# Root_v1_01.net
KiCad netlist of a schematic drawn in EAGLE
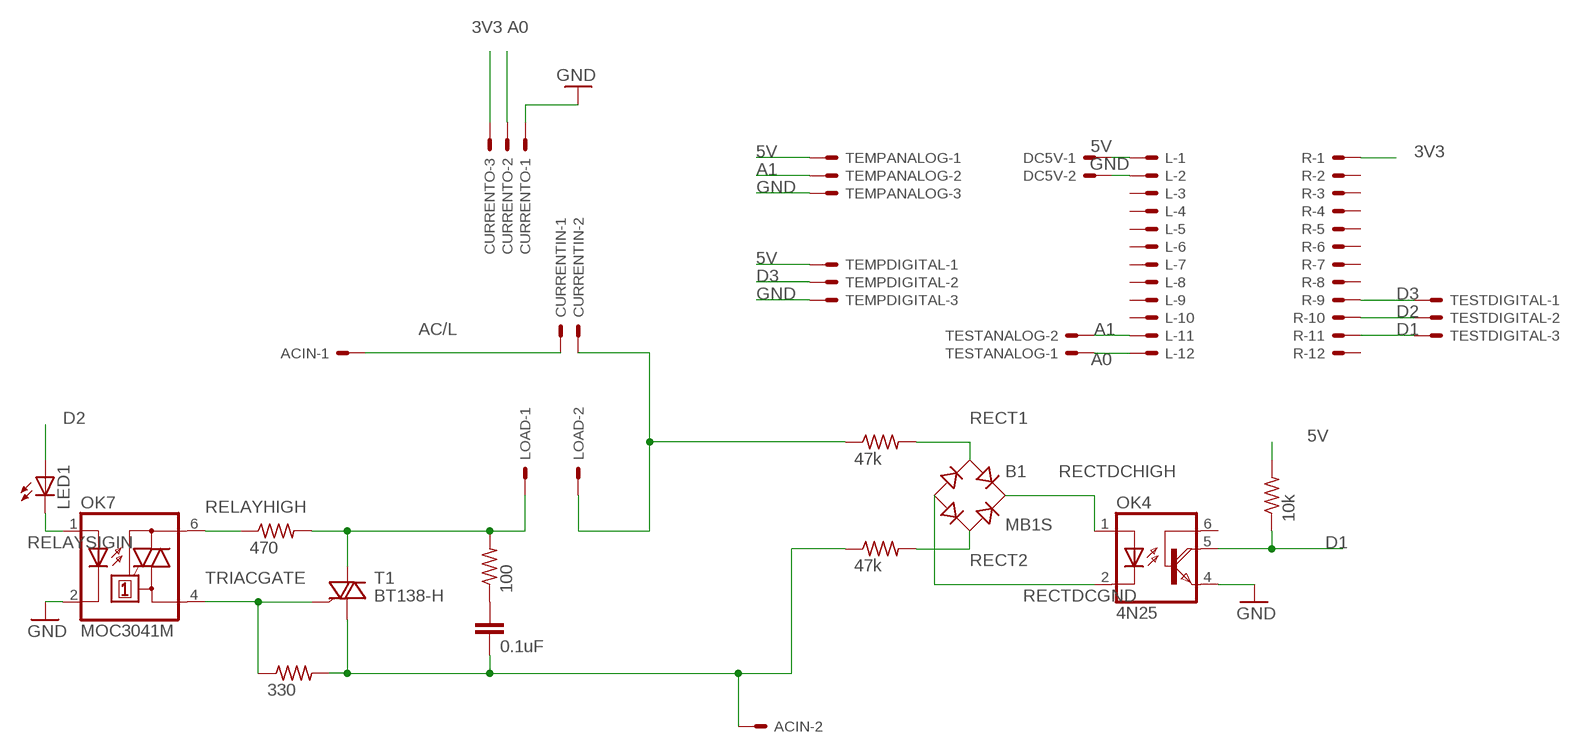
[diagram p0: schematic, sheet 1]

(export (version "E")
  (design (tool "Eeschema 10.0.6"))
  (components
    (comp (ref "ACIN")
      (value "22-23-2021")
      (footprint "eagle-import:22-23-2021")
      (fields (field (name "MF") "MOLEX"))
      (libsource (lib "eagle-import") (part "22-23-2021"))
    )
    (comp (ref "B1")
      (value "MB1S")
      (footprint "eagle-import:SOIC-4")
      (libsource (lib "eagle-import") (part "MBS1"))
    )
    (comp (ref "C4")
      (value "0.1uF")
      (footprint "eagle-import:C5B3")
      (fields (field (name "C5") "0.1uF"))
      (libsource (lib "eagle-import") (part "C5/3"))
    )
    (comp (ref "CURRENTIN")
      (value "22-23-2021")
      (footprint "eagle-import:22-23-2021")
      (fields (field (name "MF") "MOLEX"))
      (libsource (lib "eagle-import") (part "22-23-2021"))
    )
    (comp (ref "CURRENTO")
      (value "22-23-2031")
      (footprint "eagle-import:22-23-2031")
      (fields (field (name "MF") "MOLEX"))
      (libsource (lib "eagle-import") (part "22-23-2031"))
    )
    (comp (ref "DC5V")
      (value "22-23-2021")
      (footprint "eagle-import:22-23-2021")
      (fields (field (name "MF") "MOLEX"))
      (libsource (lib "eagle-import") (part "22-23-2021"))
    )
    (comp (ref "L")
      (value "22-23-2121")
      (footprint "eagle-import:22-23-2121")
      (fields (field (name "MF") "MOLEX"))
      (libsource (lib "eagle-import") (part "22-23-2121"))
    )
    (comp (ref "LED1")
      (value "N/A")
      (footprint "eagle-import:LED_LD260")
      (libsource (lib "eagle-import") (part "LED_ELD260"))
    )
    (comp (ref "LOAD")
      (value "22-23-2021")
      (footprint "eagle-import:22-23-2021")
      (fields (field (name "MF") "MOLEX"))
      (libsource (lib "eagle-import") (part "22-23-2021"))
    )
    (comp (ref "OK4")
      (value "4N25")
      (footprint "eagle-import:DIL06")
      (libsource (lib "eagle-import") (part "4N25"))
    )
    (comp (ref "OK7")
      (value "MOC3041M")
      (footprint "eagle-import:DIL06")
      (fields (field (name "MF") "FAIRCHILD SEMICONDUCTOR"))
      (libsource (lib "eagle-import") (part "MOC3041M"))
    )
    (comp (ref "R")
      (value "22-23-2121")
      (footprint "eagle-import:22-23-2121")
      (fields (field (name "MF") "MOLEX"))
      (libsource (lib "eagle-import") (part "22-23-2121"))
    )
    (comp (ref "R1")
      (value "47k")
      (footprint "eagle-import:0204_7")
      (fields (field (name "R5") "47k"))
      (libsource (lib "eagle-import") (part "R-US_0204/7"))
    )
    (comp (ref "R3")
      (value "47k")
      (footprint "eagle-import:0204_7")
      (fields (field (name "R5") "47k"))
      (libsource (lib "eagle-import") (part "R-US_0204/7"))
    )
    (comp (ref "R4")
      (value "330")
      (footprint "eagle-import:0204_7")
      (libsource (lib "eagle-import") (part "R-US_0204/7"))
    )
    (comp (ref "R6")
      (value "100")
      (footprint "eagle-import:0204_7")
      (fields (field (name "R5") "100"))
      (libsource (lib "eagle-import") (part "R-US_0204/7"))
    )
    (comp (ref "R7")
      (value "470")
      (footprint "eagle-import:0204_7")
      (fields (field (name "R5") "470"))
      (libsource (lib "eagle-import") (part "R-US_0204/7"))
    )
    (comp (ref "R8")
      (value "10k")
      (footprint "eagle-import:0204_7")
      (fields (field (name "R5") "10k"))
      (libsource (lib "eagle-import") (part "R-US_0204/7"))
    )
    (comp (ref "T1")
      (value "BT138-H")
      (footprint "eagle-import:TO220BH")
      (libsource (lib "eagle-import") (part "BT138-H"))
    )
    (comp (ref "TEMPANALOG")
      (value "22-23-2031")
      (footprint "eagle-import:22-23-2031")
      (fields (field (name "MF") "MOLEX"))
      (libsource (lib "eagle-import") (part "22-23-2031"))
    )
    (comp (ref "TEMPDIGITAL")
      (value "22-23-2031")
      (footprint "eagle-import:22-23-2031")
      (fields (field (name "MF") "MOLEX"))
      (libsource (lib "eagle-import") (part "22-23-2031"))
    )
    (comp (ref "TESTANALOG")
      (value "22-23-2021")
      (footprint "eagle-import:22-23-2021")
      (fields (field (name "MF") "MOLEX"))
      (libsource (lib "eagle-import") (part "22-23-2021"))
    )
    (comp (ref "TESTDIGITAL")
      (value "22-23-2031")
      (footprint "eagle-import:22-23-2031")
      (fields (field (name "MF") "MOLEX"))
      (libsource (lib "eagle-import") (part "22-23-2031"))
    )
  )
  (nets
    (net (code "1") (name "/3V3") (class "Default")
      (node (ref "CURRENTO") (pin "3") (pinfunction "S_3") (pintype "passive"))
      (node (ref "R") (pin "1") (pinfunction "S_1") (pintype "passive"))
    )
    (net (code "2") (name "/5V") (class "Default")
      (node (ref "DC5V") (pin "1") (pinfunction "S_1") (pintype "passive"))
      (node (ref "L") (pin "1") (pinfunction "S_1") (pintype "passive"))
      (node (ref "R8") (pin "2") (pinfunction "2_2") (pintype "passive"))
      (node (ref "TEMPANALOG") (pin "1") (pinfunction "S_1") (pintype "passive"))
      (node (ref "TEMPDIGITAL") (pin "1") (pinfunction "S_1") (pintype "passive"))
    )
    (net (code "3") (name "/A0") (class "Default")
      (node (ref "CURRENTO") (pin "2") (pinfunction "S_2") (pintype "passive"))
      (node (ref "L") (pin "12") (pinfunction "S_12") (pintype "passive"))
      (node (ref "TESTANALOG") (pin "1") (pinfunction "S_1") (pintype "passive"))
    )
    (net (code "4") (name "/A1") (class "Default")
      (node (ref "L") (pin "11") (pinfunction "S_11") (pintype "passive"))
      (node (ref "TEMPANALOG") (pin "2") (pinfunction "S_2") (pintype "passive"))
      (node (ref "TESTANALOG") (pin "2") (pinfunction "S_2") (pintype "passive"))
    )
    (net (code "5") (name "/AC{slash}L") (class "Default")
      (node (ref "ACIN") (pin "1") (pinfunction "S_1") (pintype "passive"))
      (node (ref "CURRENTIN") (pin "1") (pinfunction "S_1") (pintype "passive"))
    )
    (net (code "6") (name "/D1") (class "Default")
      (node (ref "OK4") (pin "5") (pinfunction "COL_5") (pintype "passive"))
      (node (ref "R") (pin "11") (pinfunction "S_11") (pintype "passive"))
      (node (ref "R8") (pin "1") (pinfunction "1_1") (pintype "passive"))
      (node (ref "TESTDIGITAL") (pin "3") (pinfunction "S_3") (pintype "passive"))
    )
    (net (code "7") (name "/D2") (class "Default")
      (node (ref "LED1") (pin "A") (pinfunction "A_A") (pintype "passive"))
      (node (ref "R") (pin "10") (pinfunction "S_10") (pintype "passive"))
      (node (ref "TESTDIGITAL") (pin "2") (pinfunction "S_2") (pintype "passive"))
    )
    (net (code "8") (name "/D3") (class "Default")
      (node (ref "R") (pin "9") (pinfunction "S_9") (pintype "passive"))
      (node (ref "TEMPDIGITAL") (pin "2") (pinfunction "S_2") (pintype "passive"))
      (node (ref "TESTDIGITAL") (pin "1") (pinfunction "S_1") (pintype "passive"))
    )
    (net (code "9") (name "/RECT1") (class "Default")
      (node (ref "B1") (pin "~1") (pinfunction "AC1_~1") (pintype "passive"))
      (node (ref "R1") (pin "2") (pinfunction "2_2") (pintype "passive"))
    )
    (net (code "10") (name "/RECT2") (class "Default")
      (node (ref "B1") (pin "~2") (pinfunction "AC2_~2") (pintype "passive"))
      (node (ref "R3") (pin "2") (pinfunction "2_2") (pintype "passive"))
    )
    (net (code "11") (name "/RECTDCGND") (class "Default")
      (node (ref "B1") (pin "-") (pinfunction "-_-") (pintype "passive"))
      (node (ref "OK4") (pin "2") (pinfunction "C_2") (pintype "passive"))
    )
    (net (code "12") (name "/RECTDCHIGH") (class "Default")
      (node (ref "B1") (pin "+") (pinfunction "+_+") (pintype "passive"))
      (node (ref "OK4") (pin "1") (pinfunction "A_1") (pintype "passive"))
    )
    (net (code "13") (name "/RELAYHIGH") (class "Default")
      (node (ref "OK7") (pin "6") (pinfunction "A2_6") (pintype "passive"))
      (node (ref "R7") (pin "1") (pinfunction "1_1") (pintype "passive"))
    )
    (net (code "14") (name "/RELAYSIGIN") (class "Default")
      (node (ref "LED1") (pin "K") (pinfunction "C_K") (pintype "passive"))
      (node (ref "OK7") (pin "1") (pinfunction "A_1") (pintype "passive"))
    )
    (net (code "15") (name "/TRIACGATE") (class "Default")
      (node (ref "OK7") (pin "4") (pinfunction "A1_4") (pintype "passive"))
      (node (ref "R4") (pin "1") (pinfunction "1_1") (pintype "passive"))
      (node (ref "T1") (pin "G") (pinfunction "G_G") (pintype "passive"))
    )
    (net (code "16") (name "GND") (class "Default")
      (node (ref "CURRENTO") (pin "1") (pinfunction "S_1") (pintype "passive"))
      (node (ref "DC5V") (pin "2") (pinfunction "S_2") (pintype "passive"))
      (node (ref "L") (pin "2") (pinfunction "S_2") (pintype "passive"))
      (node (ref "OK4") (pin "4") (pinfunction "E_4") (pintype "passive"))
      (node (ref "OK7") (pin "2") (pinfunction "C_2") (pintype "passive"))
      (node (ref "TEMPANALOG") (pin "3") (pinfunction "S_3") (pintype "passive"))
      (node (ref "TEMPDIGITAL") (pin "3") (pinfunction "S_3") (pintype "passive"))
    )
    (net (code "17") (name "Net-(ACINB-S)") (class "Default")
      (node (ref "ACIN") (pin "2") (pinfunction "S_2") (pintype "passive"))
      (node (ref "C4") (pin "2") (pinfunction "2_2") (pintype "passive"))
      (node (ref "R3") (pin "1") (pinfunction "1_1") (pintype "passive"))
      (node (ref "R4") (pin "2") (pinfunction "2_2") (pintype "passive"))
      (node (ref "T1") (pin "T1") (pinfunction "A1_T1") (pintype "passive"))
    )
    (net (code "18") (name "Net-(C4-Pad1)") (class "Default")
      (node (ref "C4") (pin "1") (pinfunction "1_1") (pintype "passive"))
      (node (ref "R6") (pin "1") (pinfunction "1_1") (pintype "passive"))
    )
    (net (code "19") (name "Net-(CURRENTINB-S)") (class "Default")
      (node (ref "CURRENTIN") (pin "2") (pinfunction "S_2") (pintype "passive"))
      (node (ref "LOAD") (pin "2") (pinfunction "S_2") (pintype "passive"))
      (node (ref "R1") (pin "1") (pinfunction "1_1") (pintype "passive"))
    )
    (net (code "20") (name "Net-(LOADA-S)") (class "Default")
      (node (ref "LOAD") (pin "1") (pinfunction "S_1") (pintype "passive"))
      (node (ref "R6") (pin "2") (pinfunction "2_2") (pintype "passive"))
      (node (ref "R7") (pin "2") (pinfunction "2_2") (pintype "passive"))
      (node (ref "T1") (pin "T2") (pinfunction "A2_T2") (pintype "passive"))
    )
    (net (code "21") (name "unconnected-(LB-S-Pad10)") (class "Default")
      (node (ref "L") (pin "10") (pinfunction "S_10") (pintype "passive"))
    )
    (net (code "22") (name "unconnected-(LF-S-Pad3)") (class "Default")
      (node (ref "L") (pin "3") (pinfunction "S_3") (pintype "passive"))
    )
    (net (code "23") (name "unconnected-(LG-S-Pad4)") (class "Default")
      (node (ref "L") (pin "4") (pinfunction "S_4") (pintype "passive"))
    )
    (net (code "24") (name "unconnected-(LH-S-Pad5)") (class "Default")
      (node (ref "L") (pin "5") (pinfunction "S_5") (pintype "passive"))
    )
    (net (code "25") (name "unconnected-(LI-S-Pad6)") (class "Default")
      (node (ref "L") (pin "6") (pinfunction "S_6") (pintype "passive"))
    )
    (net (code "26") (name "unconnected-(LJ-S-Pad7)") (class "Default")
      (node (ref "L") (pin "7") (pinfunction "S_7") (pintype "passive"))
    )
    (net (code "27") (name "unconnected-(LK-S-Pad8)") (class "Default")
      (node (ref "L") (pin "8") (pinfunction "S_8") (pintype "passive"))
    )
    (net (code "28") (name "unconnected-(LL-S-Pad9)") (class "Default")
      (node (ref "L") (pin "9") (pinfunction "S_9") (pintype "passive"))
    )
    (net (code "29") (name "unconnected-(OK4-B-Pad6)") (class "Default")
      (node (ref "OK4") (pin "6") (pinfunction "B_6") (pintype "passive"))
    )
    (net (code "30") (name "unconnected-(RD-S-Pad12)") (class "Default")
      (node (ref "R") (pin "12") (pinfunction "S_12") (pintype "passive"))
    )
    (net (code "31") (name "unconnected-(RE-S-Pad2)") (class "Default")
      (node (ref "R") (pin "2") (pinfunction "S_2") (pintype "passive"))
    )
    (net (code "32") (name "unconnected-(RF-S-Pad3)") (class "Default")
      (node (ref "R") (pin "3") (pinfunction "S_3") (pintype "passive"))
    )
    (net (code "33") (name "unconnected-(RG-S-Pad4)") (class "Default")
      (node (ref "R") (pin "4") (pinfunction "S_4") (pintype "passive"))
    )
    (net (code "34") (name "unconnected-(RH-S-Pad5)") (class "Default")
      (node (ref "R") (pin "5") (pinfunction "S_5") (pintype "passive"))
    )
    (net (code "35") (name "unconnected-(RI-S-Pad6)") (class "Default")
      (node (ref "R") (pin "6") (pinfunction "S_6") (pintype "passive"))
    )
    (net (code "36") (name "unconnected-(RJ-S-Pad7)") (class "Default")
      (node (ref "R") (pin "7") (pinfunction "S_7") (pintype "passive"))
    )
    (net (code "37") (name "unconnected-(RK-S-Pad8)") (class "Default")
      (node (ref "R") (pin "8") (pinfunction "S_8") (pintype "passive"))
    )
  )
)
